# TSOC_GROVEY_WIFI_R0_3.net
KiCad netlist of a schematic drawn in EAGLE
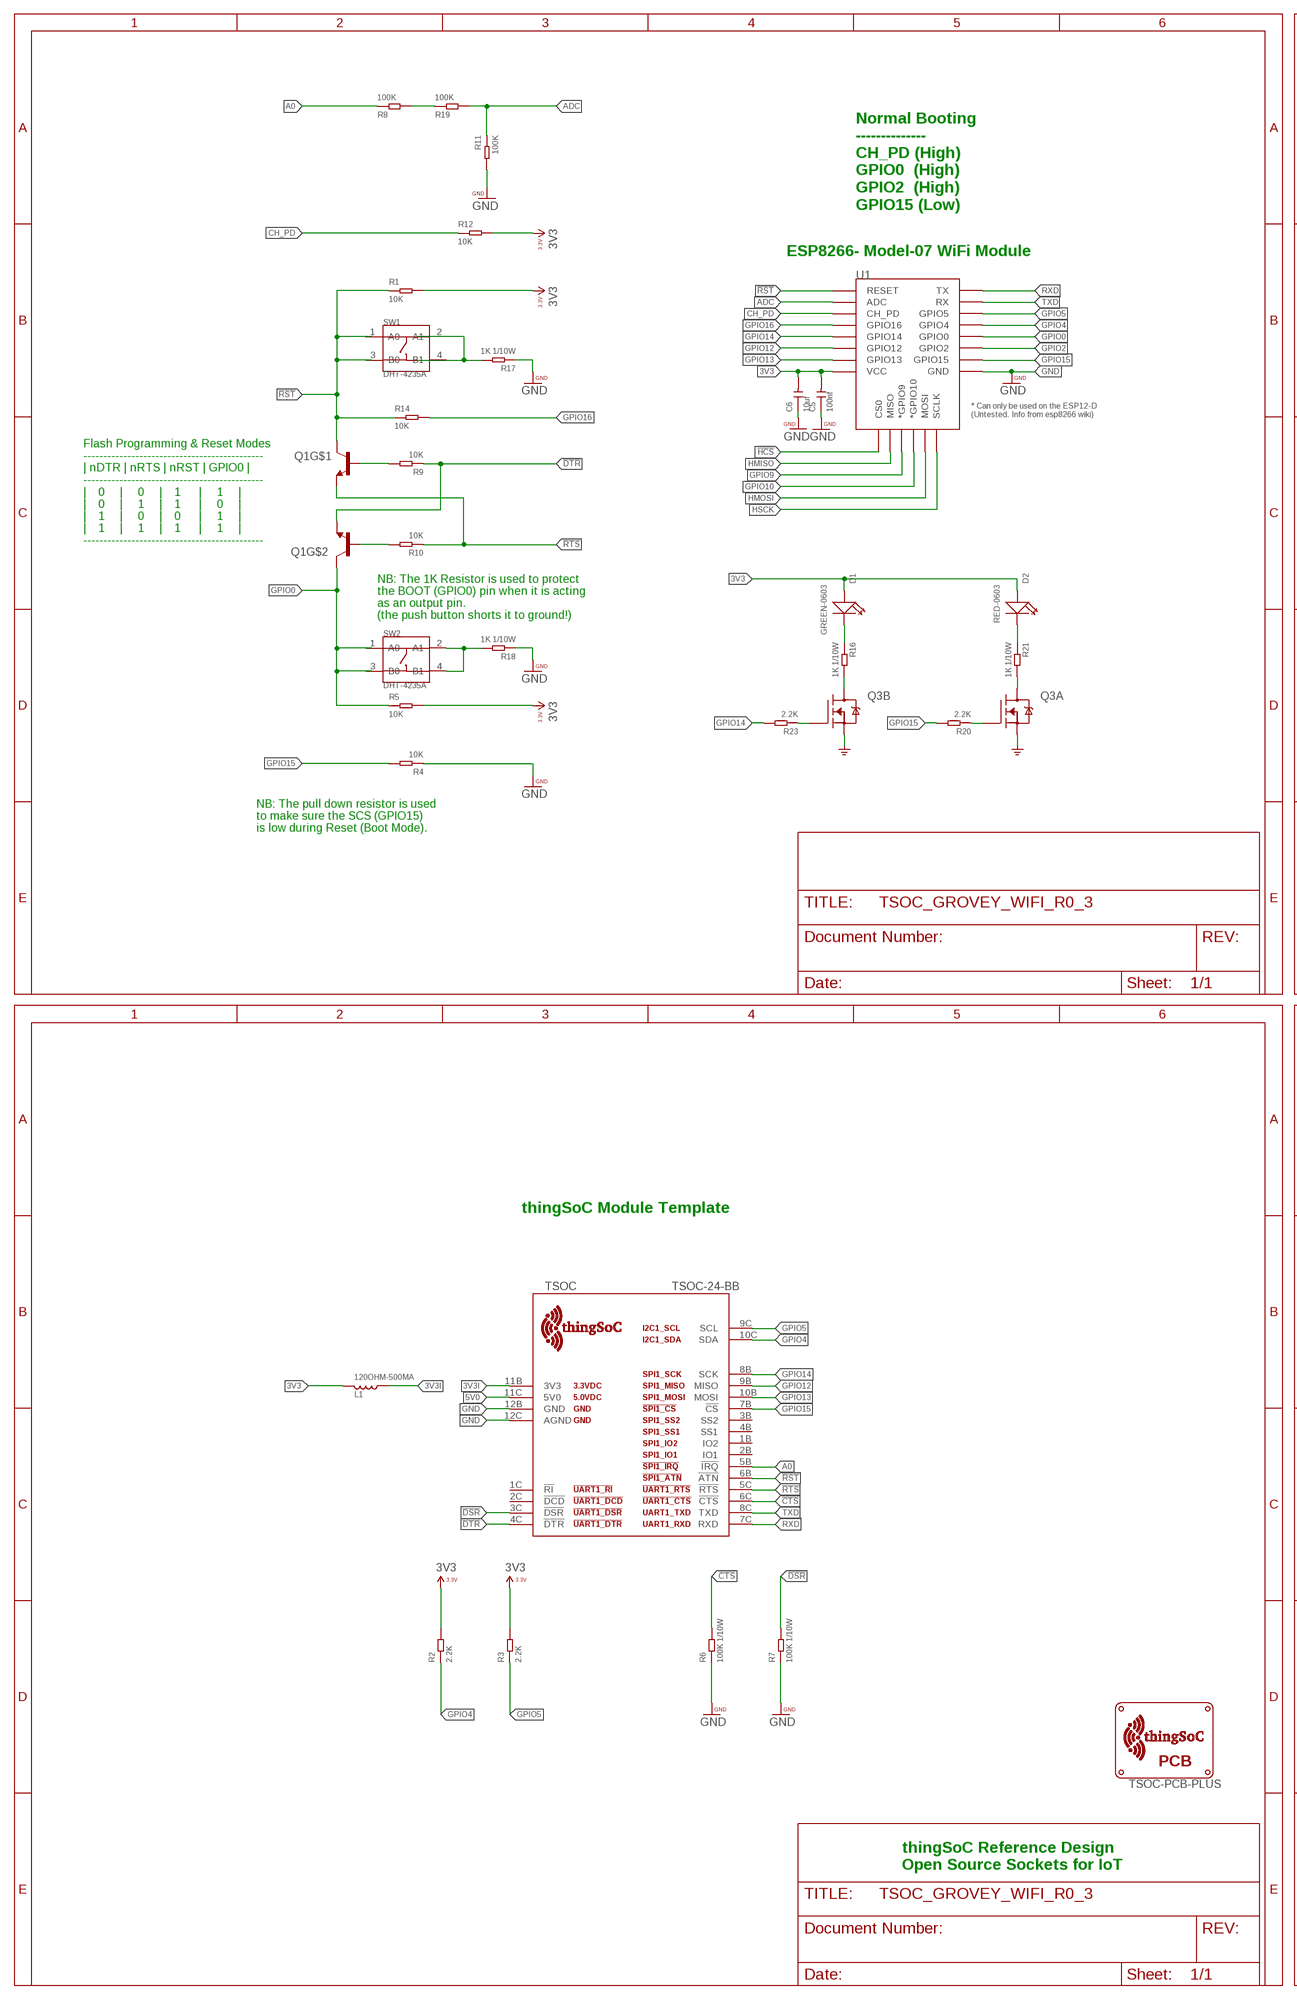
[diagram p0: schematic, sheet 1, part 1 of 2]
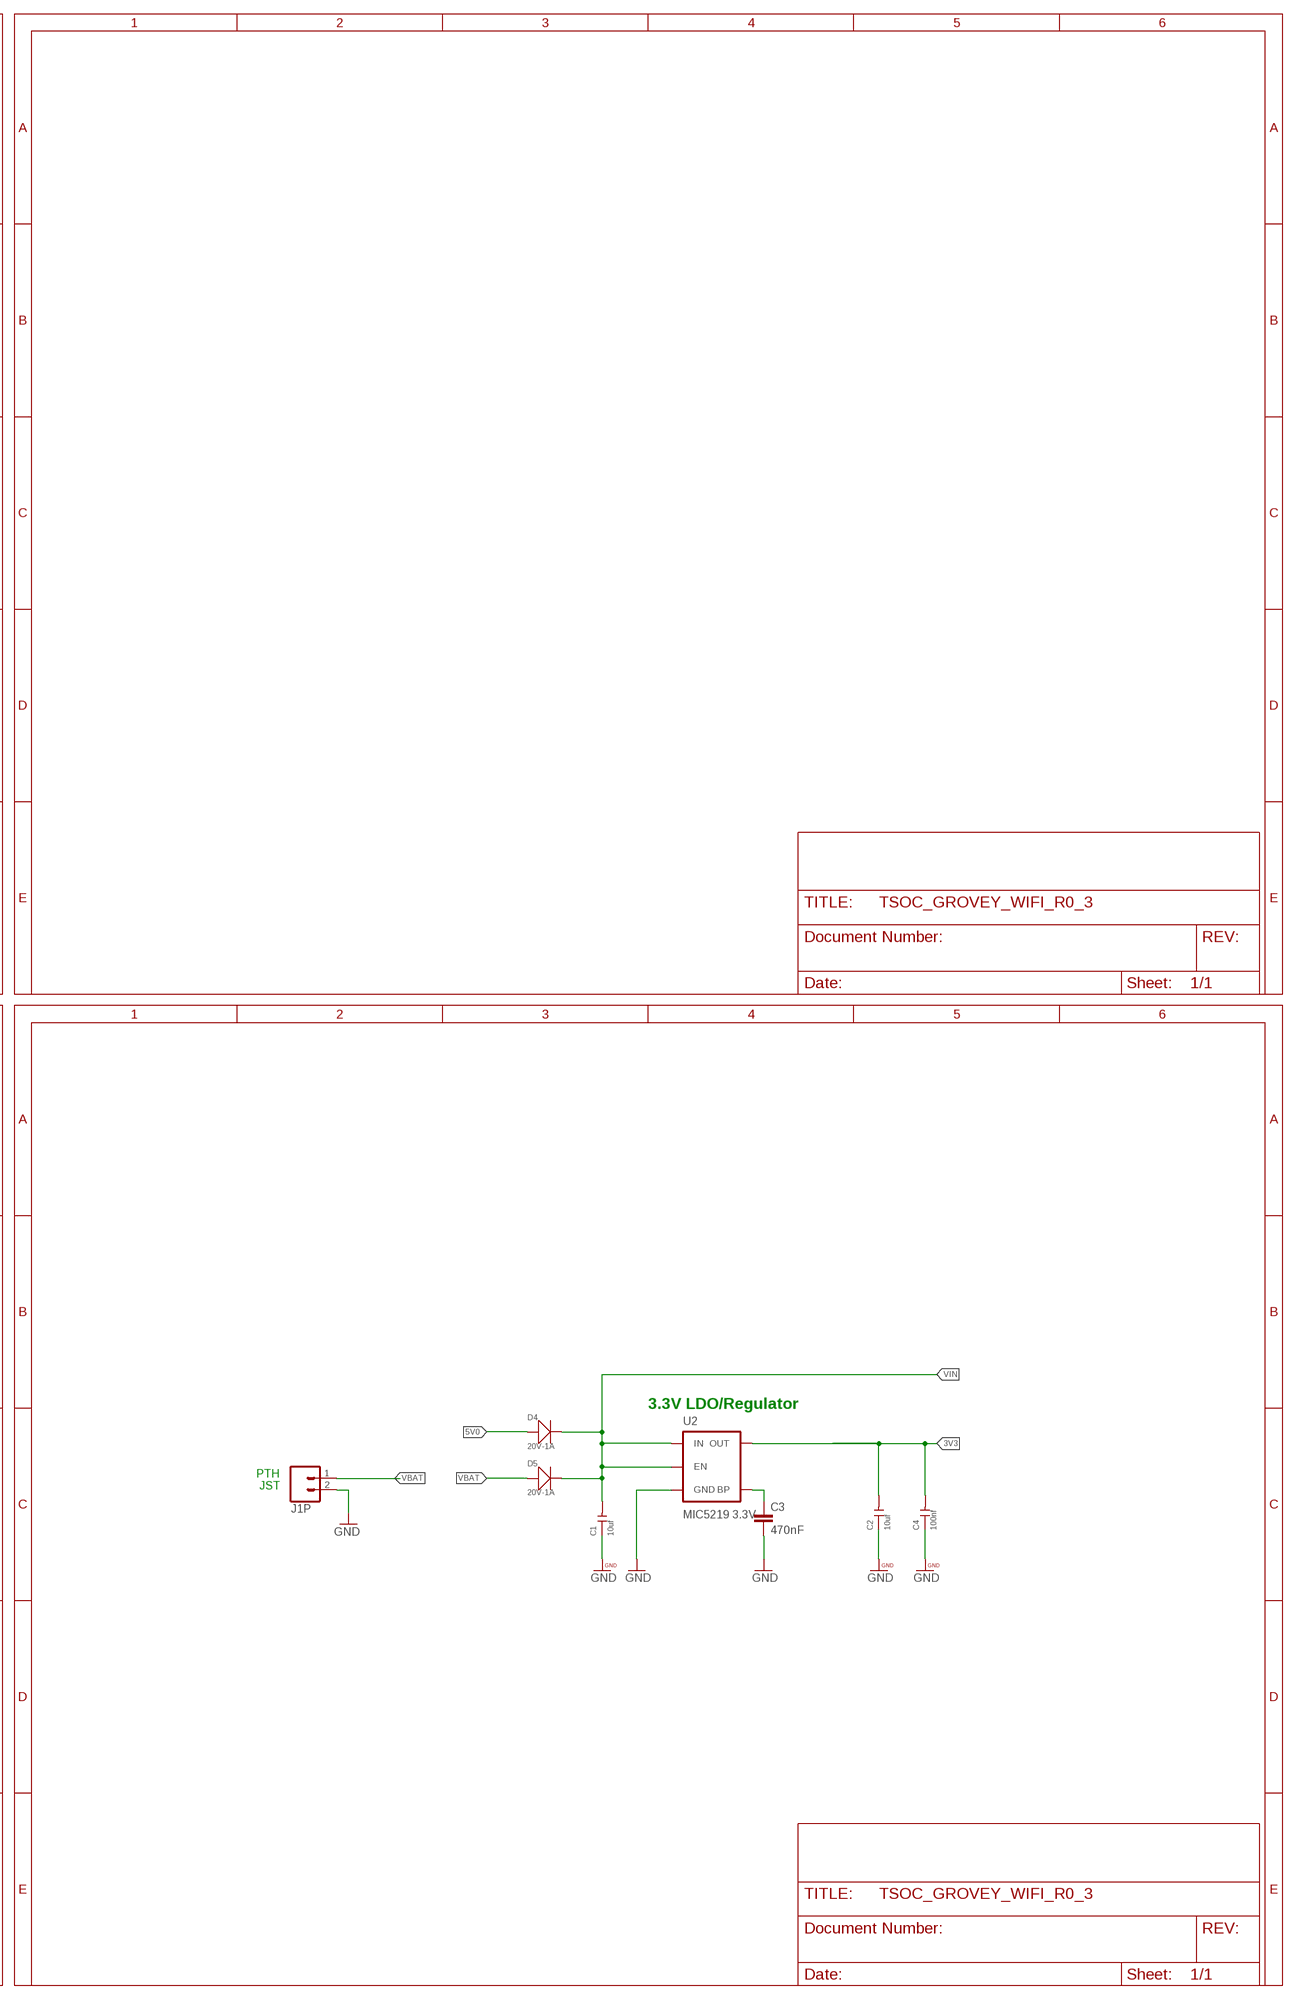
[diagram p1: schematic, sheet 1, part 2 of 2]

(export (version "E")
  (design (tool "Eeschema 10.0.6"))
  (components
    (comp (ref "C1")
      (value "10uf")
      (footprint "eagle-import:C1206")
      (fields (field (name "MPN") "CC1206KKX5R8BB106"))
      (libsource (lib "eagle-import") (part "CERAMIC-10UF-25V-10%-X5R(1206)"))
    )
    (comp (ref "C2")
      (value "10uf")
      (footprint "eagle-import:C1206")
      (fields (field (name "MPN") "CC1206KKX5R8BB106"))
      (libsource (lib "eagle-import") (part "CERAMIC-10UF-25V-10%-X5R(1206)"))
    )
    (comp (ref "C3")
      (value "470nF")
      (footprint "eagle-import:0402-CAP")
      (libsource (lib "eagle-import") (part "CAP0402-CAP"))
    )
    (comp (ref "C4")
      (value "100nf")
      (footprint "eagle-import:C0603")
      (fields (field (name "MPN") "CC0603KRX7R9BB104"))
      (libsource (lib "eagle-import") (part "CERAMIC-100NF-50V-10%-X7R(0603)"))
    )
    (comp (ref "C5")
      (value "100nf")
      (footprint "eagle-import:C0603")
      (fields (field (name "MPN") "CC0603KRX7R9BB104"))
      (libsource (lib "eagle-import") (part "CERAMIC-100NF-50V-10%-X7R(0603)"))
    )
    (comp (ref "C6")
      (value "10uf")
      (footprint "eagle-import:C1206")
      (fields (field (name "MPN") "CC1206KKX5R8BB106"))
      (libsource (lib "eagle-import") (part "CERAMIC-10UF-25V-10%-X5R(1206)"))
    )
    (comp (ref "D1")
      (value "GREEN-0603")
      (footprint "eagle-import:LED-0603")
      (fields (field (name "MPN") "19-217-G7C-AN1P2-3T"))
      (libsource (lib "eagle-import") (part "SMD-LED-CLEAR-GREEN(0603)"))
    )
    (comp (ref "D2")
      (value "RED-0603")
      (footprint "eagle-import:LED-0603")
      (fields (field (name "MPN") "19-217-R6C-AL1M2VY-3T"))
      (libsource (lib "eagle-import") (part "LED-SMD-RED-DIFFUSED(0603)"))
    )
    (comp (ref "D4")
      (value "20V-1A")
      (footprint "eagle-import:SOD-123")
      (fields (field (name "MPN") "B5819W"))
      (libsource (lib "eagle-import") (part "SMD-DIODE-SCHOTTKY-20V-1A(SOD-123)"))
    )
    (comp (ref "D5")
      (value "20V-1A")
      (footprint "eagle-import:SOD-123")
      (fields (field (name "MPN") "B5819W"))
      (libsource (lib "eagle-import") (part "SMD-DIODE-SCHOTTKY-20V-1A(SOD-123)"))
    )
    (comp (ref "J1P")
      (value "M02-JST-2-PTH-NO_SILK")
      (footprint "eagle-import:JST-2-PTH-NS")
      (libsource (lib "eagle-import") (part "M02-JST-2-PTH-NO_SILK"))
    )
    (comp (ref "L1")
      (value "120OHM-500MA")
      (footprint "eagle-import:L0603")
      (fields (field (name "MPN") "BLM18AG121SN1D"))
      (libsource (lib "eagle-import") (part "SMD-FERRITE-CHIP-120-OHM-500MA(0603)"))
    )
    (comp (ref "PCB")
      (value "TSOC-PCB-PLUS")
      (footprint "eagle-import:TSOC-BB-BRD-PLUS-DIM")
      (libsource (lib "eagle-import") (part "TSOC-PCB-PLUS"))
    )
    (comp (ref "Q1")
      (value "MMBT2222A")
      (footprint "eagle-import:SOT363")
      (libsource (lib "eagle-import") (part "MMDT3904"))
    )
    (comp (ref "Q3")
      (value "FDG1024NZ")
      (footprint "eagle-import:SOT95P280X110-6N")
      (libsource (lib "eagle-import") (part "FDG1024NZ"))
    )
    (comp (ref "R1")
      (value "10K")
      (footprint "eagle-import:R0603")
      (fields (field (name "MPN") "RC0603FR-0710KL"))
      (libsource (lib "eagle-import") (part "SMD-RES-10K-1%-1/10W(0603)"))
    )
    (comp (ref "R2")
      (value "2.2K")
      (footprint "eagle-import:R0603")
      (fields (field (name "MPN") "RC0603JR-072K2L"))
      (libsource (lib "eagle-import") (part "SMD-RES-2.2K-5%-1/10W(0603)"))
    )
    (comp (ref "R3")
      (value "2.2K")
      (footprint "eagle-import:R0603")
      (fields (field (name "MPN") "RC0603JR-072K2L"))
      (libsource (lib "eagle-import") (part "SMD-RES-2.2K-5%-1/10W(0603)"))
    )
    (comp (ref "R4")
      (value "10K")
      (footprint "eagle-import:R0603")
      (fields (field (name "MPN") "RC0603FR-0710KL"))
      (libsource (lib "eagle-import") (part "SMD-RES-10K-1%-1/10W(0603)"))
    )
    (comp (ref "R5")
      (value "10K")
      (footprint "eagle-import:R0603")
      (fields (field (name "MPN") "RC0603FR-0710KL"))
      (libsource (lib "eagle-import") (part "SMD-RES-10K-1%-1/10W(0603)"))
    )
    (comp (ref "R6")
      (value "100K 1/10W")
      (footprint "eagle-import:R0603")
      (fields (field (name "MPN") "RC0603JR-07100KL"))
      (libsource (lib "eagle-import") (part "SMD-RES-100K-5%-1/10W(0603)"))
    )
    (comp (ref "R7")
      (value "100K 1/10W")
      (footprint "eagle-import:R0603")
      (fields (field (name "MPN") "RC0603JR-07100KL"))
      (libsource (lib "eagle-import") (part "SMD-RES-100K-5%-1/10W(0603)"))
    )
    (comp (ref "R8")
      (value "100K")
      (footprint "eagle-import:R0603")
      (fields (field (name "MPN") "RC0603FR-07100KL"))
      (libsource (lib "eagle-import") (part "SMD-RES-100K-1%-1/10W(0603)"))
    )
    (comp (ref "R9")
      (value "10K")
      (footprint "eagle-import:R0603")
      (fields (field (name "MPN") "RC0603FR-0710KL"))
      (libsource (lib "eagle-import") (part "SMD-RES-10K-1%-1/10W(0603)"))
    )
    (comp (ref "R10")
      (value "10K")
      (footprint "eagle-import:R0603")
      (fields (field (name "MPN") "RC0603FR-0710KL"))
      (libsource (lib "eagle-import") (part "SMD-RES-10K-1%-1/10W(0603)"))
    )
    (comp (ref "R11")
      (value "100K")
      (footprint "eagle-import:R0603")
      (fields (field (name "MPN") "RC0603FR-07100KL"))
      (libsource (lib "eagle-import") (part "SMD-RES-100K-1%-1/10W(0603)"))
    )
    (comp (ref "R12")
      (value "10K")
      (footprint "eagle-import:R0603")
      (fields (field (name "MPN") "RC0603FR-0710KL"))
      (libsource (lib "eagle-import") (part "SMD-RES-10K-1%-1/10W(0603)"))
    )
    (comp (ref "R14")
      (value "10K")
      (footprint "eagle-import:R0603")
      (fields (field (name "MPN") "RC0603FR-0710KL"))
      (libsource (lib "eagle-import") (part "SMD-RES-10K-1%-1/10W(0603)"))
    )
    (comp (ref "R16")
      (value "1K 1/10W")
      (footprint "eagle-import:R0603")
      (fields (field (name "MPN") "RC0603JR-071KL"))
      (libsource (lib "eagle-import") (part "SMD-RES-1K-5%-1/10W(0603)"))
    )
    (comp (ref "R17")
      (value "1K 1/10W")
      (footprint "eagle-import:R0603")
      (fields (field (name "MPN") "RC0603JR-071KL"))
      (libsource (lib "eagle-import") (part "SMD-RES-1K-5%-1/10W(0603)"))
    )
    (comp (ref "R18")
      (value "1K 1/10W")
      (footprint "eagle-import:R0603")
      (fields (field (name "MPN") "RC0603JR-071KL"))
      (libsource (lib "eagle-import") (part "SMD-RES-1K-5%-1/10W(0603)"))
    )
    (comp (ref "R19")
      (value "100K")
      (footprint "eagle-import:R0603")
      (fields (field (name "MPN") "RC0603FR-07100KL"))
      (libsource (lib "eagle-import") (part "SMD-RES-100K-1%-1/10W(0603)"))
    )
    (comp (ref "R20")
      (value "2.2K")
      (footprint "eagle-import:R0603")
      (fields (field (name "MPN") "RC0603JR-072K2L"))
      (libsource (lib "eagle-import") (part "SMD-RES-2.2K-5%-1/10W(0603)"))
    )
    (comp (ref "R21")
      (value "1K 1/10W")
      (footprint "eagle-import:R0603")
      (fields (field (name "MPN") "RC0603JR-071KL"))
      (libsource (lib "eagle-import") (part "SMD-RES-1K-5%-1/10W(0603)"))
    )
    (comp (ref "R23")
      (value "2.2K")
      (footprint "eagle-import:R0603")
      (fields (field (name "MPN") "RC0603JR-072K2L"))
      (libsource (lib "eagle-import") (part "SMD-RES-2.2K-5%-1/10W(0603)"))
    )
    (comp (ref "SW1")
      (value "DHT-4235A")
      (footprint "eagle-import:SW4-SMD-4.2X3.2X2.5MM")
      (libsource (lib "eagle-import") (part "SMD-BUTTON-TOP-DHT-4235A(4P-4.2X3.2MM)"))
    )
    (comp (ref "SW2")
      (value "DHT-4235A")
      (footprint "eagle-import:SW4-SMD-4.2X3.2X2.5MM")
      (libsource (lib "eagle-import") (part "SMD-BUTTON-TOP-DHT-4235A(4P-4.2X3.2MM)"))
    )
    (comp (ref "TSOC")
      (value "TSOC-24-BB")
      (footprint "eagle-import:TSOC-BB-S24")
      (libsource (lib "eagle-import") (part "TSOC-24-BB"))
    )
    (comp (ref "U1")
      (value "ESP12ESMD")
      (footprint "eagle-import:ESP12E-SMD")
      (libsource (lib "eagle-import") (part "ESP12ESMD"))
    )
    (comp (ref "U2")
      (value "MIC5219 3.3V")
      (footprint "eagle-import:SOT23-5")
      (libsource (lib "eagle-import") (part "V_REG_MIC52193.3V"))
    )
  )
  (nets
    (net (code "1") (name "/~{CTS}") (class "Default")
      (node (ref "R6") (pin "2") (pinfunction "2_2") (pintype "passive"))
      (node (ref "TSOC") (pin "6C") (pinfunction "~{CTS}_6C") (pintype "bidirectional"))
    )
    (net (code "2") (name "/~{DSR}") (class "Default")
      (node (ref "R7") (pin "2") (pinfunction "2_2") (pintype "passive"))
      (node (ref "TSOC") (pin "3C") (pinfunction "~{DSR}_3C") (pintype "bidirectional"))
    )
    (net (code "3") (name "/~{DTR}") (class "Default")
      (node (ref "Q1") (pin "1") (pinfunction "E_1") (pintype "passive"))
      (node (ref "R9") (pin "1") (pinfunction "1_1") (pintype "passive"))
      (node (ref "TSOC") (pin "4C") (pinfunction "~{DTR}_4C") (pintype "bidirectional"))
    )
    (net (code "4") (name "/~{HCS}") (class "Default")
      (node (ref "U1") (pin "CS0") (pinfunction "CS0_CS0") (pintype "bidirectional"))
    )
    (net (code "5") (name "/~{RST}") (class "Default")
      (node (ref "Q1") (pin "3") (pinfunction "C_3") (pintype "passive"))
      (node (ref "R1") (pin "1") (pinfunction "1_1") (pintype "passive"))
      (node (ref "R14") (pin "1") (pinfunction "1_1") (pintype "passive"))
      (node (ref "SW1") (pin "1") (pinfunction "A0_1") (pintype "bidirectional"))
      (node (ref "SW1") (pin "3") (pinfunction "B0_3") (pintype "bidirectional"))
      (node (ref "TSOC") (pin "6B") (pinfunction "~{ATN}_6B") (pintype "bidirectional"))
      (node (ref "U1") (pin "RESET") (pinfunction "RESET_RESET") (pintype "bidirectional"))
    )
    (net (code "6") (name "/~{RTS}") (class "Default")
      (node (ref "Q1") (pin "4") (pinfunction "E_4") (pintype "passive"))
      (node (ref "R10") (pin "1") (pinfunction "1_1") (pintype "passive"))
      (node (ref "TSOC") (pin "5C") (pinfunction "~{RTS}_5C") (pintype "bidirectional"))
    )
    (net (code "7") (name "3V3") (class "Default")
      (node (ref "C2") (pin "2") (pinfunction "2_2") (pintype "passive"))
      (node (ref "C4") (pin "2") (pinfunction "2_2") (pintype "passive"))
      (node (ref "C5") (pin "2") (pinfunction "2_2") (pintype "passive"))
      (node (ref "C6") (pin "2") (pinfunction "2_2") (pintype "passive"))
      (node (ref "D1") (pin "+") (pinfunction "+_+") (pintype "passive"))
      (node (ref "D2") (pin "+") (pinfunction "+_+") (pintype "passive"))
      (node (ref "L1") (pin "1") (pinfunction "1_1") (pintype "passive"))
      (node (ref "R1") (pin "2") (pinfunction "2_2") (pintype "passive"))
      (node (ref "R12") (pin "2") (pinfunction "2_2") (pintype "passive"))
      (node (ref "R2") (pin "2") (pinfunction "2_2") (pintype "passive"))
      (node (ref "R3") (pin "2") (pinfunction "2_2") (pintype "passive"))
      (node (ref "R5") (pin "2") (pinfunction "2_2") (pintype "passive"))
      (node (ref "U1") (pin "VCC") (pinfunction "VCC_VCC") (pintype "bidirectional"))
      (node (ref "U2") (pin "5") (pinfunction "OUT_5") (pintype "passive"))
    )
    (net (code "8") (name "3V3I") (class "Default")
      (node (ref "L1") (pin "2") (pinfunction "2_2") (pintype "passive"))
      (node (ref "TSOC") (pin "11B") (pinfunction "3V3_11B") (pintype "bidirectional"))
    )
    (net (code "9") (name "5V0") (class "Default")
      (node (ref "D4") (pin "+") (pinfunction "+_+") (pintype "passive"))
      (node (ref "TSOC") (pin "11C") (pinfunction "5V0_11C") (pintype "bidirectional"))
    )
    (net (code "10") (name "A0") (class "Default")
      (node (ref "R8") (pin "1") (pinfunction "1_1") (pintype "passive"))
      (node (ref "TSOC") (pin "5B") (pinfunction "~{IRQ}_5B") (pintype "bidirectional"))
    )
    (net (code "11") (name "ADC") (class "Default")
      (node (ref "R11") (pin "1") (pinfunction "1_1") (pintype "passive"))
      (node (ref "R19") (pin "2") (pinfunction "2_2") (pintype "passive"))
      (node (ref "U1") (pin "ADC") (pinfunction "ADC_ADC") (pintype "bidirectional"))
    )
    (net (code "12") (name "CH_PD") (class "Default")
      (node (ref "R12") (pin "1") (pinfunction "1_1") (pintype "passive"))
      (node (ref "U1") (pin "CH_PD") (pinfunction "CH_PD_CH_PD") (pintype "bidirectional"))
    )
    (net (code "13") (name "GND") (class "Default")
      (node (ref "C1") (pin "1") (pinfunction "1_1") (pintype "passive"))
      (node (ref "C2") (pin "1") (pinfunction "1_1") (pintype "passive"))
      (node (ref "C3") (pin "2") (pinfunction "2_2") (pintype "passive"))
      (node (ref "C4") (pin "1") (pinfunction "1_1") (pintype "passive"))
      (node (ref "C5") (pin "1") (pinfunction "1_1") (pintype "passive"))
      (node (ref "C6") (pin "1") (pinfunction "1_1") (pintype "passive"))
      (node (ref "J1P") (pin "2") (pinfunction "2_2") (pintype "passive"))
      (node (ref "Q3") (pin "1") (pinfunction "S_1") (pintype "passive"))
      (node (ref "Q3") (pin "4") (pinfunction "S_4") (pintype "passive"))
      (node (ref "R11") (pin "2") (pinfunction "2_2") (pintype "passive"))
      (node (ref "R17") (pin "1") (pinfunction "1_1") (pintype "passive"))
      (node (ref "R18") (pin "1") (pinfunction "1_1") (pintype "passive"))
      (node (ref "R4") (pin "1") (pinfunction "1_1") (pintype "passive"))
      (node (ref "R6") (pin "1") (pinfunction "1_1") (pintype "passive"))
      (node (ref "R7") (pin "1") (pinfunction "1_1") (pintype "passive"))
      (node (ref "TSOC") (pin "12B") (pinfunction "GND_12B") (pintype "bidirectional"))
      (node (ref "TSOC") (pin "12C") (pinfunction "AGND_12C") (pintype "bidirectional"))
      (node (ref "U1") (pin "GND") (pinfunction "GND_GND") (pintype "bidirectional"))
      (node (ref "U2") (pin "2") (pinfunction "GND_2") (pintype "input"))
    )
    (net (code "14") (name "GPIO0") (class "Default")
      (node (ref "Q1") (pin "6") (pinfunction "C_6") (pintype "passive"))
      (node (ref "R5") (pin "1") (pinfunction "1_1") (pintype "passive"))
      (node (ref "SW2") (pin "1") (pinfunction "A0_1") (pintype "bidirectional"))
      (node (ref "SW2") (pin "3") (pinfunction "B0_3") (pintype "bidirectional"))
      (node (ref "U1") (pin "GPIO0") (pinfunction "GPIO0_GPIO0") (pintype "bidirectional"))
    )
    (net (code "15") (name "GPIO2") (class "Default")
      (node (ref "U1") (pin "GPIO2") (pinfunction "GPIO2_GPIO2") (pintype "bidirectional"))
    )
    (net (code "16") (name "GPIO4") (class "Default")
      (node (ref "R2") (pin "1") (pinfunction "1_1") (pintype "passive"))
      (node (ref "TSOC") (pin "10C") (pinfunction "SDA_10C") (pintype "bidirectional"))
      (node (ref "U1") (pin "GPIO4") (pinfunction "GPIO4_GPIO4") (pintype "bidirectional"))
    )
    (net (code "17") (name "GPIO5") (class "Default")
      (node (ref "R3") (pin "1") (pinfunction "1_1") (pintype "passive"))
      (node (ref "TSOC") (pin "9C") (pinfunction "SCL_9C") (pintype "bidirectional"))
      (node (ref "U1") (pin "GPIO5") (pinfunction "GPIO5_GPIO5") (pintype "bidirectional"))
    )
    (net (code "18") (name "GPIO9") (class "Default")
      (node (ref "U1") (pin "GPIO9") (pinfunction "*GPIO9_GPIO9") (pintype "bidirectional"))
    )
    (net (code "19") (name "GPIO10") (class "Default")
      (node (ref "U1") (pin "GPIO10") (pinfunction "*GPIO10_GPIO10") (pintype "bidirectional"))
    )
    (net (code "20") (name "GPIO12") (class "Default")
      (node (ref "TSOC") (pin "9B") (pinfunction "MISO_9B") (pintype "bidirectional"))
      (node (ref "U1") (pin "GPIO12") (pinfunction "GPIO12_GPIO12") (pintype "bidirectional"))
    )
    (net (code "21") (name "GPIO13") (class "Default")
      (node (ref "TSOC") (pin "10B") (pinfunction "MOSI_10B") (pintype "bidirectional"))
      (node (ref "U1") (pin "GPIO13") (pinfunction "GPIO13_GPIO13") (pintype "bidirectional"))
    )
    (net (code "22") (name "GPIO14") (class "Default")
      (node (ref "R23") (pin "2") (pinfunction "2_2") (pintype "passive"))
      (node (ref "TSOC") (pin "8B") (pinfunction "SCK_8B") (pintype "bidirectional"))
      (node (ref "U1") (pin "GPIO14") (pinfunction "GPIO14_GPIO14") (pintype "bidirectional"))
    )
    (net (code "23") (name "GPIO15") (class "Default")
      (node (ref "R20") (pin "2") (pinfunction "2_2") (pintype "passive"))
      (node (ref "R4") (pin "2") (pinfunction "2_2") (pintype "passive"))
      (node (ref "TSOC") (pin "7B") (pinfunction "~{CS}_7B") (pintype "bidirectional"))
      (node (ref "U1") (pin "GPIO15") (pinfunction "GPIO15_GPIO15") (pintype "bidirectional"))
    )
    (net (code "24") (name "GPIO16") (class "Default")
      (node (ref "R14") (pin "2") (pinfunction "2_2") (pintype "passive"))
      (node (ref "U1") (pin "GPIO16") (pinfunction "GPIO16_GPIO16") (pintype "bidirectional"))
    )
    (net (code "25") (name "HMISO") (class "Default")
      (node (ref "U1") (pin "MISO") (pinfunction "MISO_MISO") (pintype "bidirectional"))
    )
    (net (code "26") (name "HMOSI") (class "Default")
      (node (ref "U1") (pin "MOSI") (pinfunction "MOSI_MOSI") (pintype "bidirectional"))
    )
    (net (code "27") (name "HSCK") (class "Default")
      (node (ref "U1") (pin "SCLK") (pinfunction "SCLK_SCLK") (pintype "bidirectional"))
    )
    (net (code "28") (name "Net-(D1-Pad-)") (class "Default")
      (node (ref "D1") (pin "-") (pinfunction "-_-") (pintype "passive"))
      (node (ref "R16") (pin "1") (pinfunction "1_1") (pintype "passive"))
    )
    (net (code "29") (name "Net-(D2-Pad-)") (class "Default")
      (node (ref "D2") (pin "-") (pinfunction "-_-") (pintype "passive"))
      (node (ref "R21") (pin "1") (pinfunction "1_1") (pintype "passive"))
    )
    (net (code "30") (name "Net-(Q1A-B)") (class "Default")
      (node (ref "Q1") (pin "5") (pinfunction "B_5") (pintype "passive"))
      (node (ref "R9") (pin "2") (pinfunction "2_2") (pintype "passive"))
    )
    (net (code "31") (name "Net-(Q1B-B)") (class "Default")
      (node (ref "Q1") (pin "2") (pinfunction "B_2") (pintype "passive"))
      (node (ref "R10") (pin "2") (pinfunction "2_2") (pintype "passive"))
    )
    (net (code "32") (name "Net-(Q3A-D)") (class "Default")
      (node (ref "Q3") (pin "6") (pinfunction "D_6") (pintype "passive"))
      (node (ref "R21") (pin "2") (pinfunction "2_2") (pintype "passive"))
    )
    (net (code "33") (name "Net-(Q3A-G)") (class "Default")
      (node (ref "Q3") (pin "2") (pinfunction "G_2") (pintype "passive"))
      (node (ref "R20") (pin "1") (pinfunction "1_1") (pintype "passive"))
    )
    (net (code "34") (name "Net-(Q3B-D)") (class "Default")
      (node (ref "Q3") (pin "3") (pinfunction "D_3") (pintype "passive"))
      (node (ref "R16") (pin "2") (pinfunction "2_2") (pintype "passive"))
    )
    (net (code "35") (name "Net-(Q3B-G)") (class "Default")
      (node (ref "Q3") (pin "5") (pinfunction "G_5") (pintype "passive"))
      (node (ref "R23") (pin "1") (pinfunction "1_1") (pintype "passive"))
    )
    (net (code "36") (name "Net-(R19-Pad1)") (class "Default")
      (node (ref "R19") (pin "1") (pinfunction "1_1") (pintype "passive"))
      (node (ref "R8") (pin "2") (pinfunction "2_2") (pintype "passive"))
    )
    (net (code "37") (name "Net-(SW1-A1)") (class "Default")
      (node (ref "R17") (pin "2") (pinfunction "2_2") (pintype "passive"))
      (node (ref "SW1") (pin "2") (pinfunction "A1_2") (pintype "bidirectional"))
      (node (ref "SW1") (pin "4") (pinfunction "B1_4") (pintype "bidirectional"))
    )
    (net (code "38") (name "Net-(SW2-A1)") (class "Default")
      (node (ref "R18") (pin "2") (pinfunction "2_2") (pintype "passive"))
      (node (ref "SW2") (pin "2") (pinfunction "A1_2") (pintype "bidirectional"))
      (node (ref "SW2") (pin "4") (pinfunction "B1_4") (pintype "bidirectional"))
    )
    (net (code "39") (name "Net-(U2-BP)") (class "Default")
      (node (ref "C3") (pin "1") (pinfunction "1_1") (pintype "passive"))
      (node (ref "U2") (pin "4") (pinfunction "BP_4") (pintype "input"))
    )
    (net (code "40") (name "RXD") (class "Default")
      (node (ref "TSOC") (pin "7C") (pinfunction "RXD_7C") (pintype "bidirectional"))
      (node (ref "U1") (pin "TXD0") (pinfunction "TX_TXD0") (pintype "bidirectional"))
    )
    (net (code "41") (name "TXD") (class "Default")
      (node (ref "TSOC") (pin "8C") (pinfunction "TXD_8C") (pintype "bidirectional"))
      (node (ref "U1") (pin "RXD0") (pinfunction "RX_RXD0") (pintype "bidirectional"))
    )
    (net (code "42") (name "VBAT") (class "Default")
      (node (ref "D5") (pin "+") (pinfunction "+_+") (pintype "passive"))
      (node (ref "J1P") (pin "1") (pinfunction "1_1") (pintype "passive"))
    )
    (net (code "43") (name "VIN") (class "Default")
      (node (ref "C1") (pin "2") (pinfunction "2_2") (pintype "passive"))
      (node (ref "D4") (pin "-") (pinfunction "-_-") (pintype "passive"))
      (node (ref "D5") (pin "-") (pinfunction "-_-") (pintype "passive"))
      (node (ref "U2") (pin "1") (pinfunction "IN_1") (pintype "input"))
      (node (ref "U2") (pin "3") (pinfunction "EN_3") (pintype "input"))
    )
    (net (code "44") (name "unconnected-(TSOC-IO1-Pad2B)") (class "Default")
      (node (ref "TSOC") (pin "2B") (pinfunction "IO1_2B") (pintype "bidirectional"))
    )
    (net (code "45") (name "unconnected-(TSOC-IO2-Pad1B)") (class "Default")
      (node (ref "TSOC") (pin "1B") (pinfunction "IO2_1B") (pintype "bidirectional"))
    )
    (net (code "46") (name "unconnected-(TSOC-SS1-Pad4B)") (class "Default")
      (node (ref "TSOC") (pin "4B") (pinfunction "SS1_4B") (pintype "bidirectional"))
    )
    (net (code "47") (name "unconnected-(TSOC-SS2-Pad3B)") (class "Default")
      (node (ref "TSOC") (pin "3B") (pinfunction "SS2_3B") (pintype "bidirectional"))
    )
    (net (code "48") (name "unconnected-(TSOC-~{DCD}-Pad2C)") (class "Default")
      (node (ref "TSOC") (pin "2C") (pinfunction "~{DCD}_2C") (pintype "bidirectional"))
    )
    (net (code "49") (name "unconnected-(TSOC-~{RI}-Pad1C)") (class "Default")
      (node (ref "TSOC") (pin "1C") (pinfunction "~{RI}_1C") (pintype "bidirectional"))
    )
  )
)
